# MSP430.net
KiCad netlist of a schematic drawn in Altium Designer
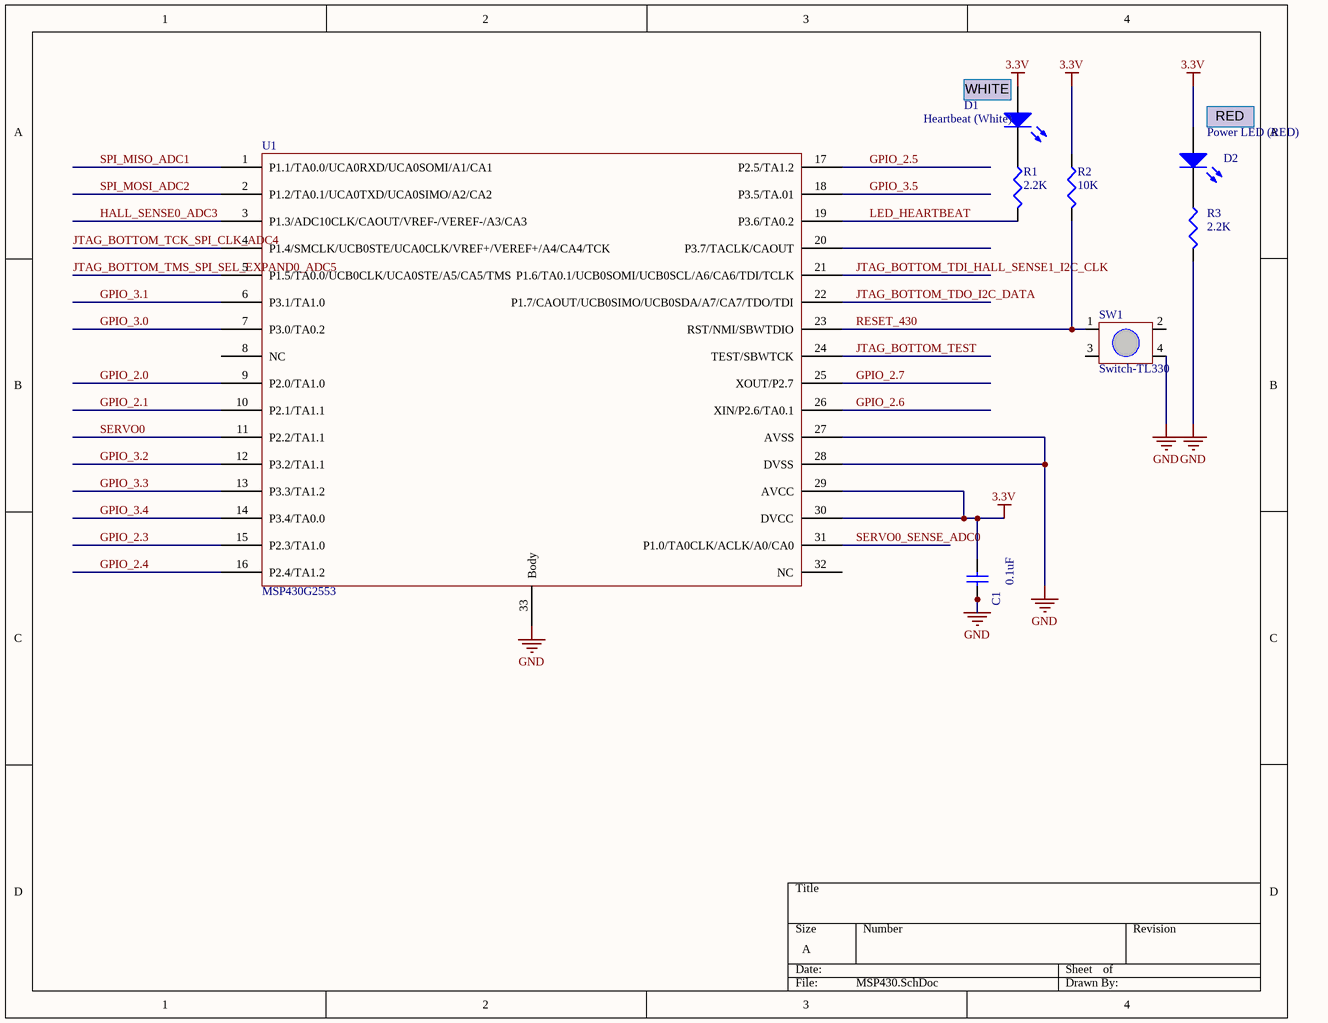
[diagram p0: MSP430.SchDoc]

(export (version "E")
  (design (tool "Eeschema 10.0.6"))
  (components
    (comp (ref "C1")
      (value "0.1uF")
      (footprint "CAPC1005L")
      (description "Capacitor (Semiconductor SIM Model)")
      (fields (field (name "Comment") "Cap Semi") (field (name "PUBLISHER") "Altium Limited"))
      (libsource (lib "Miscellaneous Devices") (part "Cap Semi"))
    )
    (comp (ref "D1")
      (value "Heartbeat (White)")
      (footprint "SurfaceMount(603)")
      (libsource (lib "mrone") (part "LED"))
    )
    (comp (ref "D2")
      (value "Power LED (RED)")
      (footprint "SurfaceMount(603)")
      (libsource (lib "mrone") (part "LED"))
    )
    (comp (ref "R1")
      (value "2.2K")
      (footprint "J1-0603")
      (description "Resistor")
      (fields (field (name "Comment") "DiodeRes") (field (name "PUBLISHER") "Altium Limited"))
      (libsource (lib "Miscellaneous Devices") (part "Res3"))
    )
    (comp (ref "R2")
      (value "10K")
      (footprint "J1-0603")
      (description "Resistor")
      (fields (field (name "Comment") "ResetRes") (field (name "PUBLISHER") "Altium Limited"))
      (libsource (lib "Miscellaneous Devices") (part "Res3"))
    )
    (comp (ref "R3")
      (value "2.2K")
      (footprint "J1-0603")
      (description "Resistor")
      (fields (field (name "Comment") "DiodeRes") (field (name "PUBLISHER") "Altium Limited"))
      (libsource (lib "Miscellaneous Devices") (part "Res3"))
    )
    (comp (ref "SW1")
      (value "Switch-TL330")
      (footprint "SwitchTall-TL330")
      (libsource (lib "mrone") (part "Switch-TL330"))
    )
    (comp (ref "U1")
      (value "MSP430G2553")
      (footprint "QFN-32")
      (libsource (lib "mrone") (part "MSP430G2553"))
    )
  )
  (nets
    (net (code "1") (name "/GPIO_2.0") (class "Default")
      (node (ref "U1") (pin "9") (pinfunction "P2.0/TA1.0_9") (pintype "passive"))
    )
    (net (code "2") (name "/GPIO_2.1") (class "Default")
      (node (ref "U1") (pin "10") (pinfunction "P2.1/TA1.1_10") (pintype "passive"))
    )
    (net (code "3") (name "/GPIO_2.3") (class "Default")
      (node (ref "U1") (pin "15") (pinfunction "P2.3/TA1.0_15") (pintype "passive"))
    )
    (net (code "4") (name "/GPIO_2.4") (class "Default")
      (node (ref "U1") (pin "16") (pinfunction "P2.4/TA1.2_16") (pintype "passive"))
    )
    (net (code "5") (name "/GPIO_2.5") (class "Default")
      (node (ref "U1") (pin "17") (pinfunction "P2.5/TA1.2_17") (pintype "passive"))
    )
    (net (code "6") (name "/GPIO_2.6") (class "Default")
      (node (ref "U1") (pin "26") (pinfunction "XIN/P2.6/TA0.1_26") (pintype "passive"))
    )
    (net (code "7") (name "/GPIO_2.7") (class "Default")
      (node (ref "U1") (pin "25") (pinfunction "XOUT/P2.7_25") (pintype "passive"))
    )
    (net (code "8") (name "/GPIO_3.0") (class "Default")
      (node (ref "U1") (pin "7") (pinfunction "P3.0/TA0.2_7") (pintype "passive"))
    )
    (net (code "9") (name "/GPIO_3.1") (class "Default")
      (node (ref "U1") (pin "6") (pinfunction "P3.1/TA1.0_6") (pintype "passive"))
    )
    (net (code "10") (name "/GPIO_3.2") (class "Default")
      (node (ref "U1") (pin "12") (pinfunction "P3.2/TA1.1_12") (pintype "passive"))
    )
    (net (code "11") (name "/GPIO_3.3") (class "Default")
      (node (ref "U1") (pin "13") (pinfunction "P3.3/TA1.2_13") (pintype "passive"))
    )
    (net (code "12") (name "/GPIO_3.4") (class "Default")
      (node (ref "U1") (pin "14") (pinfunction "P3.4/TA0.0_14") (pintype "passive"))
    )
    (net (code "13") (name "/GPIO_3.5") (class "Default")
      (node (ref "U1") (pin "18") (pinfunction "P3.5/TA.01_18") (pintype "passive"))
    )
    (net (code "14") (name "/HALL_SENSE0_ADC3") (class "Default")
      (node (ref "U1") (pin "3") (pinfunction "P1.3/ADC10CLK/CAOUT/VREF-/VEREF-/A3/CA3_3") (pintype "passive"))
    )
    (net (code "15") (name "/JTAG_BOTTOM_TCK_SPI_CLK_ADC4") (class "Default")
      (node (ref "U1") (pin "4") (pinfunction "P1.4/SMCLK/UCB0STE/UCA0CLK/VREF+/VEREF+/A4/CA4/TCK_4") (pintype "passive"))
    )
    (net (code "16") (name "/JTAG_BOTTOM_TDI_HALL_SENSE1_I2C_CLK") (class "Default")
      (node (ref "U1") (pin "21") (pinfunction "P1.6/TA0.1/UCB0SOMI/UCB0SCL/A6/CA6/TDI/TCLK_21") (pintype "passive"))
    )
    (net (code "17") (name "/JTAG_BOTTOM_TDO_I2C_DATA") (class "Default")
      (node (ref "U1") (pin "22") (pinfunction "P1.7/CAOUT/UCB0SIMO/UCB0SDA/A7/CA7/TDO/TDI_22") (pintype "passive"))
    )
    (net (code "18") (name "/JTAG_BOTTOM_TEST") (class "Default")
      (node (ref "U1") (pin "24") (pinfunction "TEST/SBWTCK_24") (pintype "passive"))
    )
    (net (code "19") (name "/JTAG_BOTTOM_TMS_SPI_SEL_EXPAND0_ADC5") (class "Default")
      (node (ref "U1") (pin "5") (pinfunction "P1.5/TA0.0/UCB0CLK/UCA0STE/A5/CA5/TMS_5") (pintype "passive"))
    )
    (net (code "20") (name "/LED_HEARTBEAT") (class "Default")
      (node (ref "R1") (pin "2") (pinfunction "2_2") (pintype "passive"))
      (node (ref "U1") (pin "19") (pinfunction "P3.6/TA0.2_19") (pintype "passive"))
    )
    (net (code "21") (name "/RESET_430") (class "Default")
      (node (ref "R2") (pin "2") (pinfunction "2_2") (pintype "passive"))
      (node (ref "SW1") (pin "1") (pinfunction "1_1") (pintype "passive"))
      (node (ref "U1") (pin "23") (pinfunction "RST/NMI/SBWTDIO_23") (pintype "passive"))
    )
    (net (code "22") (name "/SERVO0") (class "Default")
      (node (ref "U1") (pin "11") (pinfunction "P2.2/TA1.1_11") (pintype "passive"))
    )
    (net (code "23") (name "/SERVO0_SENSE_ADC0") (class "Default")
      (node (ref "U1") (pin "31") (pinfunction "P1.0/TA0CLK/ACLK/A0/CA0_31") (pintype "passive"))
    )
    (net (code "24") (name "/SPI_MISO_ADC1") (class "Default")
      (node (ref "U1") (pin "1") (pinfunction "P1.1/TA0.0/UCA0RXD/UCA0SOMI/A1/CA1_1") (pintype "passive"))
    )
    (net (code "25") (name "/SPI_MOSI_ADC2") (class "Default")
      (node (ref "U1") (pin "2") (pinfunction "P1.2/TA0.1/UCA0TXD/UCA0SIMO/A2/CA2_2") (pintype "passive"))
    )
    (net (code "26") (name "3.3V") (class "Default")
      (node (ref "C1") (pin "2") (pinfunction "2_2") (pintype "passive"))
      (node (ref "D1") (pin "1") (pinfunction "A_1") (pintype "passive"))
      (node (ref "D2") (pin "1") (pinfunction "A_1") (pintype "passive"))
      (node (ref "R2") (pin "1") (pinfunction "1_1") (pintype "passive"))
      (node (ref "U1") (pin "29") (pinfunction "AVCC_29") (pintype "passive"))
      (node (ref "U1") (pin "30") (pinfunction "DVCC_30") (pintype "passive"))
    )
    (net (code "27") (name "GND") (class "Default")
      (node (ref "C1") (pin "1") (pinfunction "1_1") (pintype "passive"))
      (node (ref "R3") (pin "2") (pinfunction "2_2") (pintype "passive"))
      (node (ref "SW1") (pin "4") (pinfunction "4_4") (pintype "passive"))
      (node (ref "U1") (pin "27") (pinfunction "AVSS_27") (pintype "passive"))
      (node (ref "U1") (pin "28") (pinfunction "DVSS_28") (pintype "passive"))
      (node (ref "U1") (pin "33") (pinfunction "Body_33") (pintype "passive"))
    )
    (net (code "28") (name "Net-(D1-K)") (class "Default")
      (node (ref "D1") (pin "2") (pinfunction "K_2") (pintype "passive"))
      (node (ref "R1") (pin "1") (pinfunction "1_1") (pintype "passive"))
    )
    (net (code "29") (name "Net-(D2-K)") (class "Default")
      (node (ref "D2") (pin "2") (pinfunction "K_2") (pintype "passive"))
      (node (ref "R3") (pin "1") (pinfunction "1_1") (pintype "passive"))
    )
    (net (code "30") (name "unconnected-(SW1-Pad2)") (class "Default")
      (node (ref "SW1") (pin "2") (pinfunction "2_2") (pintype "passive"))
    )
    (net (code "31") (name "unconnected-(SW1-Pad3)") (class "Default")
      (node (ref "SW1") (pin "3") (pinfunction "3_3") (pintype "passive"))
    )
    (net (code "32") (name "unconnected-(U1-NC-Pad8)") (class "Default")
      (node (ref "U1") (pin "8") (pinfunction "NC_8") (pintype "passive"))
    )
    (net (code "33") (name "unconnected-(U1-NC-Pad32)") (class "Default")
      (node (ref "U1") (pin "32") (pinfunction "NC_32") (pintype "passive"))
    )
    (net (code "34") (name "unconnected-(U1-P3.7{slash}TACLK{slash}CAOUT-Pad20)") (class "Default")
      (node (ref "U1") (pin "20") (pinfunction "P3.7/TACLK/CAOUT_20") (pintype "passive"))
    )
  )
)
